# tick-mk-5_0_1.net
KiCad netlist of a schematic drawn in EAGLE
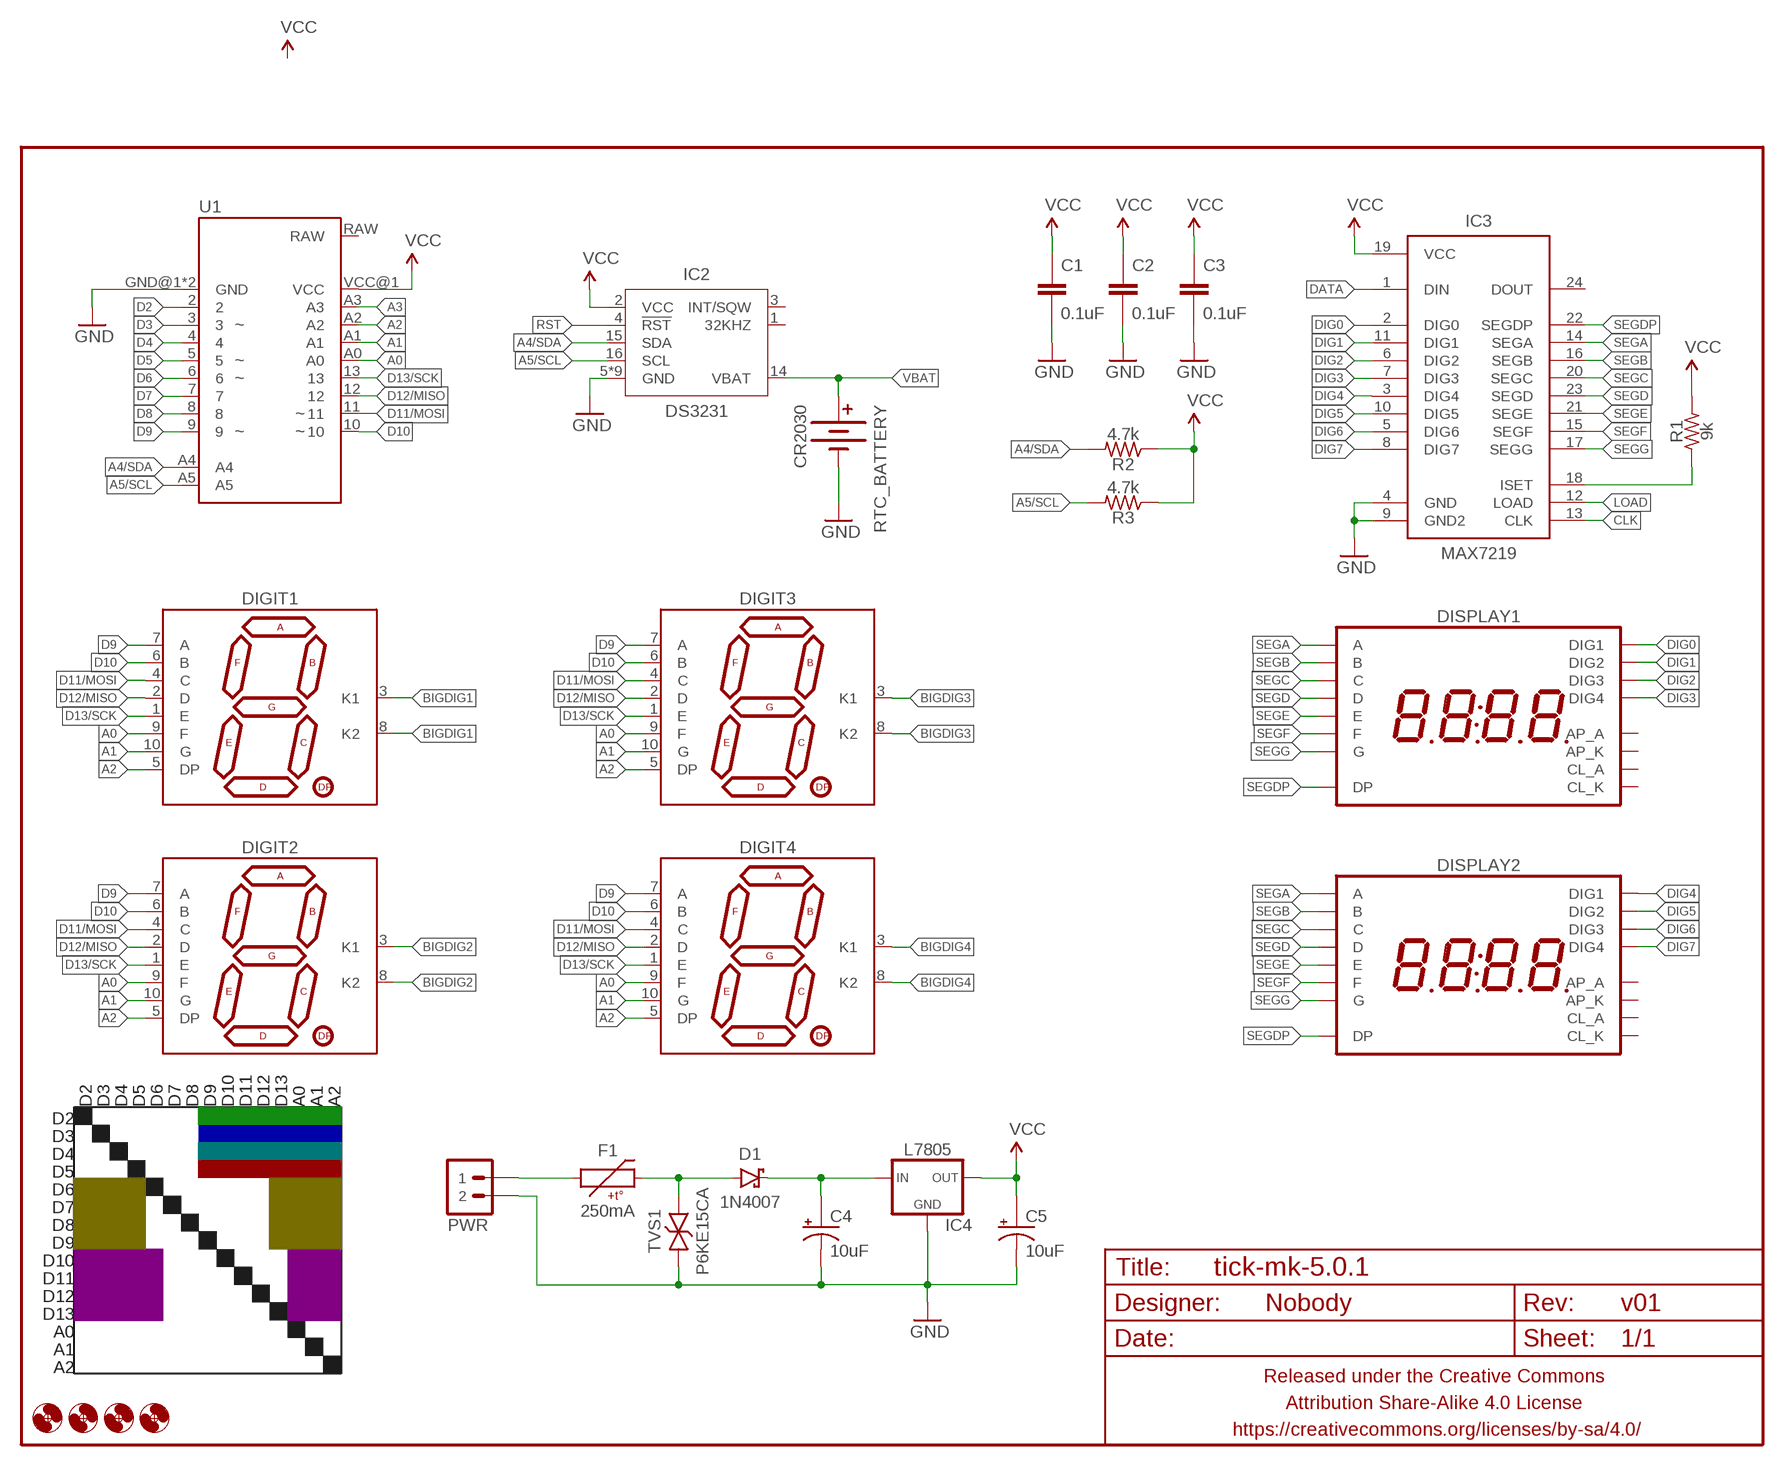
[diagram p0: schematic, sheet 1]

(export (version "E")
  (design (tool "Eeschema 10.0.6"))
  (components
    (comp (ref "C1")
      (value "0.1uF")
      (footprint "eagle-import:C025-024X044")
      (libsource (lib "eagle-import") (part "CAPACITOR-CERAMIC025-024X044"))
    )
    (comp (ref "C2")
      (value "0.1uF")
      (footprint "eagle-import:C025-024X044")
      (libsource (lib "eagle-import") (part "CAPACITOR-CERAMIC025-024X044"))
    )
    (comp (ref "C3")
      (value "0.1uF")
      (footprint "eagle-import:C0603")
      (libsource (lib "eagle-import") (part "CAPACITOR-CERAMICC0603"))
    )
    (comp (ref "C4")
      (value "10uF")
      (footprint "eagle-import:E2-5")
      (libsource (lib "eagle-import") (part "CAPACITOR-POLARIZEDE2-5"))
    )
    (comp (ref "C5")
      (value "10uF")
      (footprint "eagle-import:E2-5")
      (libsource (lib "eagle-import") (part "CAPACITOR-POLARIZEDE2-5"))
    )
    (comp (ref "D1")
      (value "1N4007")
      (footprint "eagle-import:DIODE-10.16MM")
      (libsource (lib "eagle-import") (part "DIODE-SCHOTTKYPTH-10.16MM"))
    )
    (comp (ref "DIGIT1")
      (value "7SEG_1DIGPTH-25.4MM-BARE")
      (footprint "eagle-import:7SEG_1DIG_25.4MM_NOSILK")
      (libsource (lib "eagle-import") (part "7SEG_1DIGPTH-25.4MM-BARE"))
    )
    (comp (ref "DIGIT2")
      (value "7SEG_1DIGPTH-25.4MM-BARE")
      (footprint "eagle-import:7SEG_1DIG_25.4MM_NOSILK")
      (libsource (lib "eagle-import") (part "7SEG_1DIGPTH-25.4MM-BARE"))
    )
    (comp (ref "DIGIT3")
      (value "7SEG_1DIGPTH-25.4MM-BARE")
      (footprint "eagle-import:7SEG_1DIG_25.4MM_NOSILK")
      (libsource (lib "eagle-import") (part "7SEG_1DIGPTH-25.4MM-BARE"))
    )
    (comp (ref "DIGIT4")
      (value "7SEG_1DIGPTH-25.4MM-BARE")
      (footprint "eagle-import:7SEG_1DIG_25.4MM_NOSILK")
      (libsource (lib "eagle-import") (part "7SEG_1DIGPTH-25.4MM-BARE"))
    )
    (comp (ref "DISPLAY1")
      (value "7SEG_4DIGIT_COLON_APOS")
      (footprint "eagle-import:7SEG_4DIG_10MM")
      (libsource (lib "eagle-import") (part "7SEG_4DIGIT_COLON_APOS"))
    )
    (comp (ref "DISPLAY2")
      (value "7SEG_4DIGIT_COLON_APOS")
      (footprint "eagle-import:7SEG_4DIG_10MM")
      (libsource (lib "eagle-import") (part "7SEG_4DIGIT_COLON_APOS"))
    )
    (comp (ref "F1")
      (value "250mA")
      (footprint "eagle-import:PTC-PTH-5.08MM")
      (libsource (lib "eagle-import") (part "PTCPTH-5.08MM"))
    )
    (comp (ref "FRAME1")
      (value "FRAME-LETTERNO_PACKAGE")
      (footprint "eagle-import:DUMMY")
      (fields (field (name "DESIGNER") "Nobody"))
      (libsource (lib "eagle-import") (part "FRAME-LETTERNO_PACKAGE"))
    )
    (comp (ref "H1")
      (value "HOLE2,5")
      (footprint "eagle-import:2,5")
      (libsource (lib "eagle-import") (part "HOLE2,5"))
    )
    (comp (ref "H2")
      (value "HOLE2,5")
      (footprint "eagle-import:2,5")
      (libsource (lib "eagle-import") (part "HOLE2,5"))
    )
    (comp (ref "H3")
      (value "HOLE2,5")
      (footprint "eagle-import:2,5")
      (libsource (lib "eagle-import") (part "HOLE2,5"))
    )
    (comp (ref "H4")
      (value "HOLE2,5")
      (footprint "eagle-import:2,5")
      (libsource (lib "eagle-import") (part "HOLE2,5"))
    )
    (comp (ref "IC2")
      (value "DS3231")
      (footprint "eagle-import:SO16W")
      (libsource (lib "eagle-import") (part "DS3231"))
    )
    (comp (ref "IC3")
      (value "MAX7219")
      (footprint "eagle-import:SO24W")
      (libsource (lib "eagle-import") (part "MAX7219SOIC-W"))
    )
    (comp (ref "IC4")
      (value "L7805")
      (footprint "eagle-import:TO220-IGO-THERMPAD")
      (libsource (lib "eagle-import") (part "V_REG_78XXTO-220-THERMPAD"))
    )
    (comp (ref "PWR")
      (value "M02JST-PTH-RA-L+")
      (footprint "eagle-import:JST-2-PH-RA-PTH-L+")
      (libsource (lib "eagle-import") (part "M02JST-PTH-RA-L+"))
    )
    (comp (ref "R1")
      (value "9k")
      (footprint "eagle-import:R0603")
      (libsource (lib "eagle-import") (part "RESISTORR0603"))
    )
    (comp (ref "R2")
      (value "4.7k")
      (footprint "eagle-import:RESISTOR-AXIAL-PTH-6.35MM")
      (libsource (lib "eagle-import") (part "RESISTORPTH-AXIAL-6.35MM"))
    )
    (comp (ref "R3")
      (value "4.7k")
      (footprint "eagle-import:RESISTOR-AXIAL-PTH-6.35MM")
      (libsource (lib "eagle-import") (part "RESISTORPTH-AXIAL-6.35MM"))
    )
    (comp (ref "RTC_BATTERY")
      (value "CR2030")
      (footprint "eagle-import:BATTCON_20MM_MINE_STAHPIT")
      (libsource (lib "eagle-import") (part "BATTERY20MM_SMD_TIGHT"))
    )
    (comp (ref "TVS1")
      (value "P6KE15CA")
      (footprint "eagle-import:DO-41-TVS-BI-10.16MM")
      (libsource (lib "eagle-import") (part "TVSDO-41-10.16MM"))
    )
    (comp (ref "U1")
      (value "ARDUINO_PRO_MINI_TICK2")
      (footprint "eagle-import:ARDUINO_PRO_MINI_TICK2")
      (libsource (lib "eagle-import") (part "ARDUINO_PRO_MINI_TICK2"))
    )
  )
  (nets
    (net (code "1") (name "A0") (class "Default")
      (node (ref "DIGIT1") (pin "9") (pinfunction "F_9") (pintype "bidirectional"))
      (node (ref "DIGIT2") (pin "9") (pinfunction "F_9") (pintype "bidirectional"))
      (node (ref "DIGIT3") (pin "9") (pinfunction "F_9") (pintype "bidirectional"))
      (node (ref "DIGIT4") (pin "9") (pinfunction "F_9") (pintype "bidirectional"))
      (node (ref "U1") (pin "A0") (pinfunction "A0_A0") (pintype "bidirectional"))
    )
    (net (code "2") (name "A1") (class "Default")
      (node (ref "DIGIT1") (pin "10") (pinfunction "G_10") (pintype "bidirectional"))
      (node (ref "DIGIT2") (pin "10") (pinfunction "G_10") (pintype "bidirectional"))
      (node (ref "DIGIT3") (pin "10") (pinfunction "G_10") (pintype "bidirectional"))
      (node (ref "DIGIT4") (pin "10") (pinfunction "G_10") (pintype "bidirectional"))
      (node (ref "U1") (pin "A1") (pinfunction "A1_A1") (pintype "bidirectional"))
    )
    (net (code "3") (name "A2") (class "Default")
      (node (ref "DIGIT1") (pin "5") (pinfunction "DP_5") (pintype "bidirectional"))
      (node (ref "DIGIT2") (pin "5") (pinfunction "DP_5") (pintype "bidirectional"))
      (node (ref "DIGIT3") (pin "5") (pinfunction "DP_5") (pintype "bidirectional"))
      (node (ref "DIGIT4") (pin "5") (pinfunction "DP_5") (pintype "bidirectional"))
      (node (ref "U1") (pin "A2") (pinfunction "A2_A2") (pintype "bidirectional"))
    )
    (net (code "4") (name "A3") (class "Default")
      (node (ref "U1") (pin "A3") (pinfunction "A3_A3") (pintype "bidirectional"))
    )
    (net (code "5") (name "A4{slash}SDA") (class "Default")
      (node (ref "IC2") (pin "15") (pinfunction "SDA_15") (pintype "bidirectional"))
      (node (ref "R2") (pin "P$2") (pinfunction "2_P$2") (pintype "passive"))
      (node (ref "U1") (pin "A4") (pinfunction "A4_A4") (pintype "bidirectional"))
    )
    (net (code "6") (name "A5{slash}SCL") (class "Default")
      (node (ref "IC2") (pin "16") (pinfunction "SCL_16") (pintype "bidirectional"))
      (node (ref "R3") (pin "P$2") (pinfunction "2_P$2") (pintype "passive"))
      (node (ref "U1") (pin "A5") (pinfunction "A5_A5") (pintype "bidirectional"))
    )
    (net (code "7") (name "BIGDIG1") (class "Default")
      (node (ref "DIGIT1") (pin "3") (pinfunction "K1_3") (pintype "bidirectional"))
      (node (ref "DIGIT1") (pin "8") (pinfunction "K2_8") (pintype "bidirectional"))
    )
    (net (code "8") (name "BIGDIG2") (class "Default")
      (node (ref "DIGIT2") (pin "3") (pinfunction "K1_3") (pintype "bidirectional"))
      (node (ref "DIGIT2") (pin "8") (pinfunction "K2_8") (pintype "bidirectional"))
    )
    (net (code "9") (name "BIGDIG3") (class "Default")
      (node (ref "DIGIT3") (pin "3") (pinfunction "K1_3") (pintype "bidirectional"))
      (node (ref "DIGIT3") (pin "8") (pinfunction "K2_8") (pintype "bidirectional"))
    )
    (net (code "10") (name "BIGDIG4") (class "Default")
      (node (ref "DIGIT4") (pin "3") (pinfunction "K1_3") (pintype "bidirectional"))
      (node (ref "DIGIT4") (pin "8") (pinfunction "K2_8") (pintype "bidirectional"))
    )
    (net (code "11") (name "CLK") (class "Default")
      (node (ref "IC3") (pin "13") (pinfunction "CLK_13") (pintype "bidirectional"))
    )
    (net (code "12") (name "D2") (class "Default")
      (node (ref "U1") (pin "2") (pinfunction "2_2") (pintype "bidirectional"))
    )
    (net (code "13") (name "D3") (class "Default")
      (node (ref "U1") (pin "3") (pinfunction "3_3") (pintype "bidirectional"))
    )
    (net (code "14") (name "D4") (class "Default")
      (node (ref "U1") (pin "4") (pinfunction "4_4") (pintype "bidirectional"))
    )
    (net (code "15") (name "D5") (class "Default")
      (node (ref "U1") (pin "5") (pinfunction "5_5") (pintype "bidirectional"))
    )
    (net (code "16") (name "D6") (class "Default")
      (node (ref "U1") (pin "6") (pinfunction "6_6") (pintype "bidirectional"))
    )
    (net (code "17") (name "D7") (class "Default")
      (node (ref "U1") (pin "7") (pinfunction "7_7") (pintype "bidirectional"))
    )
    (net (code "18") (name "D8") (class "Default")
      (node (ref "U1") (pin "8") (pinfunction "8_8") (pintype "bidirectional"))
    )
    (net (code "19") (name "D9") (class "Default")
      (node (ref "DIGIT1") (pin "7") (pinfunction "A_7") (pintype "bidirectional"))
      (node (ref "DIGIT2") (pin "7") (pinfunction "A_7") (pintype "bidirectional"))
      (node (ref "DIGIT3") (pin "7") (pinfunction "A_7") (pintype "bidirectional"))
      (node (ref "DIGIT4") (pin "7") (pinfunction "A_7") (pintype "bidirectional"))
      (node (ref "U1") (pin "9") (pinfunction "9_9") (pintype "bidirectional"))
    )
    (net (code "20") (name "D10") (class "Default")
      (node (ref "DIGIT1") (pin "6") (pinfunction "B_6") (pintype "bidirectional"))
      (node (ref "DIGIT2") (pin "6") (pinfunction "B_6") (pintype "bidirectional"))
      (node (ref "DIGIT3") (pin "6") (pinfunction "B_6") (pintype "bidirectional"))
      (node (ref "DIGIT4") (pin "6") (pinfunction "B_6") (pintype "bidirectional"))
      (node (ref "U1") (pin "10") (pinfunction "10_10") (pintype "bidirectional"))
    )
    (net (code "21") (name "D11{slash}MOSI") (class "Default")
      (node (ref "DIGIT1") (pin "4") (pinfunction "C_4") (pintype "bidirectional"))
      (node (ref "DIGIT2") (pin "4") (pinfunction "C_4") (pintype "bidirectional"))
      (node (ref "DIGIT3") (pin "4") (pinfunction "C_4") (pintype "bidirectional"))
      (node (ref "DIGIT4") (pin "4") (pinfunction "C_4") (pintype "bidirectional"))
      (node (ref "U1") (pin "11") (pinfunction "11_11") (pintype "bidirectional"))
    )
    (net (code "22") (name "D12{slash}MISO") (class "Default")
      (node (ref "DIGIT1") (pin "2") (pinfunction "D_2") (pintype "bidirectional"))
      (node (ref "DIGIT2") (pin "2") (pinfunction "D_2") (pintype "bidirectional"))
      (node (ref "DIGIT3") (pin "2") (pinfunction "D_2") (pintype "bidirectional"))
      (node (ref "DIGIT4") (pin "2") (pinfunction "D_2") (pintype "bidirectional"))
      (node (ref "U1") (pin "12") (pinfunction "12_12") (pintype "bidirectional"))
    )
    (net (code "23") (name "D13{slash}SCK") (class "Default")
      (node (ref "DIGIT1") (pin "1") (pinfunction "E_1") (pintype "bidirectional"))
      (node (ref "DIGIT2") (pin "1") (pinfunction "E_1") (pintype "bidirectional"))
      (node (ref "DIGIT3") (pin "1") (pinfunction "E_1") (pintype "bidirectional"))
      (node (ref "DIGIT4") (pin "1") (pinfunction "E_1") (pintype "bidirectional"))
      (node (ref "U1") (pin "13") (pinfunction "13_13") (pintype "bidirectional"))
    )
    (net (code "24") (name "DATA") (class "Default")
      (node (ref "IC3") (pin "1") (pinfunction "DIN_1") (pintype "bidirectional"))
    )
    (net (code "25") (name "DIG0") (class "Default")
      (node (ref "DISPLAY1") (pin "1") (pinfunction "DIG1_1") (pintype "passive"))
      (node (ref "IC3") (pin "2") (pinfunction "DIG0_2") (pintype "bidirectional"))
    )
    (net (code "26") (name "DIG1") (class "Default")
      (node (ref "DISPLAY1") (pin "2") (pinfunction "DIG2_2") (pintype "passive"))
      (node (ref "IC3") (pin "11") (pinfunction "DIG1_11") (pintype "bidirectional"))
    )
    (net (code "27") (name "DIG2") (class "Default")
      (node (ref "DISPLAY1") (pin "6") (pinfunction "DIG3_6") (pintype "passive"))
      (node (ref "IC3") (pin "6") (pinfunction "DIG2_6") (pintype "bidirectional"))
    )
    (net (code "28") (name "DIG3") (class "Default")
      (node (ref "DISPLAY1") (pin "8") (pinfunction "DIG4_8") (pintype "passive"))
      (node (ref "IC3") (pin "7") (pinfunction "DIG3_7") (pintype "bidirectional"))
    )
    (net (code "29") (name "DIG4") (class "Default")
      (node (ref "DISPLAY2") (pin "1") (pinfunction "DIG1_1") (pintype "passive"))
      (node (ref "IC3") (pin "3") (pinfunction "DIG4_3") (pintype "bidirectional"))
    )
    (net (code "30") (name "DIG5") (class "Default")
      (node (ref "DISPLAY2") (pin "2") (pinfunction "DIG2_2") (pintype "passive"))
      (node (ref "IC3") (pin "10") (pinfunction "DIG5_10") (pintype "bidirectional"))
    )
    (net (code "31") (name "DIG6") (class "Default")
      (node (ref "DISPLAY2") (pin "6") (pinfunction "DIG3_6") (pintype "passive"))
      (node (ref "IC3") (pin "5") (pinfunction "DIG6_5") (pintype "bidirectional"))
    )
    (net (code "32") (name "DIG7") (class "Default")
      (node (ref "DISPLAY2") (pin "8") (pinfunction "DIG4_8") (pintype "passive"))
      (node (ref "IC3") (pin "8") (pinfunction "DIG7_8") (pintype "bidirectional"))
    )
    (net (code "33") (name "GND") (class "Default")
      (node (ref "C1") (pin "2") (pinfunction "2_2") (pintype "passive"))
      (node (ref "C2") (pin "2") (pinfunction "2_2") (pintype "passive"))
      (node (ref "C3") (pin "2") (pinfunction "2_2") (pintype "passive"))
      (node (ref "C4") (pin "-") (pinfunction "-_-") (pintype "passive"))
      (node (ref "C5") (pin "-") (pinfunction "-_-") (pintype "passive"))
      (node (ref "IC2") (pin "10") (pinfunction "GND_10") (pintype "bidirectional"))
      (node (ref "IC2") (pin "11") (pinfunction "GND_11") (pintype "bidirectional"))
      (node (ref "IC2") (pin "12") (pinfunction "GND_12") (pintype "bidirectional"))
      (node (ref "IC2") (pin "13") (pinfunction "GND_13") (pintype "bidirectional"))
      (node (ref "IC2") (pin "5") (pinfunction "GND_5") (pintype "bidirectional"))
      (node (ref "IC2") (pin "6") (pinfunction "GND_6") (pintype "bidirectional"))
      (node (ref "IC2") (pin "7") (pinfunction "GND_7") (pintype "bidirectional"))
      (node (ref "IC2") (pin "8") (pinfunction "GND_8") (pintype "bidirectional"))
      (node (ref "IC2") (pin "9") (pinfunction "GND_9") (pintype "bidirectional"))
      (node (ref "IC3") (pin "4") (pinfunction "GND_4") (pintype "bidirectional"))
      (node (ref "IC3") (pin "9") (pinfunction "GND2_9") (pintype "bidirectional"))
      (node (ref "IC4") (pin "4") (pinfunction "GND_4") (pintype "bidirectional"))
      (node (ref "IC4") (pin "GND") (pinfunction "GND_GND") (pintype "bidirectional"))
      (node (ref "PWR") (pin "2") (pinfunction "2_2") (pintype "passive"))
      (node (ref "RTC_BATTERY") (pin "BOTTOM") (pinfunction "-_BOTTOM") (pintype "power_in"))
      (node (ref "TVS1") (pin "P$1") (pinfunction "1_P$1") (pintype "passive"))
      (node (ref "U1") (pin "GND@1") (pinfunction "GND_GND@1") (pintype "bidirectional"))
      (node (ref "U1") (pin "GND@2") (pinfunction "GND_GND@2") (pintype "bidirectional"))
    )
    (net (code "34") (name "LOAD") (class "Default")
      (node (ref "IC3") (pin "12") (pinfunction "LOAD_12") (pintype "bidirectional"))
    )
    (net (code "35") (name "Net-(C4-Pad+)") (class "Default")
      (node (ref "C4") (pin "+") (pinfunction "+_+") (pintype "passive"))
      (node (ref "D1") (pin "C") (pinfunction "C_C") (pintype "passive"))
      (node (ref "IC4") (pin "IN") (pinfunction "IN_IN") (pintype "bidirectional"))
    )
    (net (code "36") (name "Net-(F1-1)") (class "Default")
      (node (ref "F1") (pin "P$1") (pinfunction "1_P$1") (pintype "passive"))
      (node (ref "PWR") (pin "1") (pinfunction "1_1") (pintype "passive"))
    )
    (net (code "37") (name "Net-(F1-2)") (class "Default")
      (node (ref "D1") (pin "A") (pinfunction "A_A") (pintype "passive"))
      (node (ref "F1") (pin "P$2") (pinfunction "2_P$2") (pintype "passive"))
      (node (ref "TVS1") (pin "P$2") (pinfunction "2_P$2") (pintype "passive"))
    )
    (net (code "38") (name "Net-(IC3-ISET)") (class "Default")
      (node (ref "IC3") (pin "18") (pinfunction "ISET_18") (pintype "bidirectional"))
      (node (ref "R1") (pin "1") (pinfunction "1_1") (pintype "passive"))
    )
    (net (code "39") (name "RST") (class "Default")
      (node (ref "IC2") (pin "4") (pinfunction "~{RST}_4") (pintype "bidirectional"))
    )
    (net (code "40") (name "SEGA") (class "Default")
      (node (ref "DISPLAY1") (pin "14") (pinfunction "A_14") (pintype "passive"))
      (node (ref "DISPLAY2") (pin "14") (pinfunction "A_14") (pintype "passive"))
      (node (ref "IC3") (pin "14") (pinfunction "SEGA_14") (pintype "bidirectional"))
    )
    (net (code "41") (name "SEGB") (class "Default")
      (node (ref "DISPLAY1") (pin "16") (pinfunction "B_16") (pintype "passive"))
      (node (ref "DISPLAY2") (pin "16") (pinfunction "B_16") (pintype "passive"))
      (node (ref "IC3") (pin "16") (pinfunction "SEGB_16") (pintype "bidirectional"))
    )
    (net (code "42") (name "SEGC") (class "Default")
      (node (ref "DISPLAY1") (pin "13") (pinfunction "C_13") (pintype "passive"))
      (node (ref "DISPLAY2") (pin "13") (pinfunction "C_13") (pintype "passive"))
      (node (ref "IC3") (pin "20") (pinfunction "SEGC_20") (pintype "bidirectional"))
    )
    (net (code "43") (name "SEGD") (class "Default")
      (node (ref "DISPLAY1") (pin "3") (pinfunction "D_3") (pintype "passive"))
      (node (ref "DISPLAY2") (pin "3") (pinfunction "D_3") (pintype "passive"))
      (node (ref "IC3") (pin "23") (pinfunction "SEGD_23") (pintype "bidirectional"))
    )
    (net (code "44") (name "SEGDP") (class "Default")
      (node (ref "DISPLAY1") (pin "7") (pinfunction "DP_7") (pintype "passive"))
      (node (ref "DISPLAY2") (pin "7") (pinfunction "DP_7") (pintype "passive"))
      (node (ref "IC3") (pin "22") (pinfunction "SEGDP_22") (pintype "bidirectional"))
    )
    (net (code "45") (name "SEGE") (class "Default")
      (node (ref "DISPLAY1") (pin "5") (pinfunction "E_5") (pintype "passive"))
      (node (ref "DISPLAY2") (pin "5") (pinfunction "E_5") (pintype "passive"))
      (node (ref "IC3") (pin "21") (pinfunction "SEGE_21") (pintype "bidirectional"))
    )
    (net (code "46") (name "SEGF") (class "Default")
      (node (ref "DISPLAY1") (pin "11") (pinfunction "F_11") (pintype "passive"))
      (node (ref "DISPLAY2") (pin "11") (pinfunction "F_11") (pintype "passive"))
      (node (ref "IC3") (pin "15") (pinfunction "SEGF_15") (pintype "bidirectional"))
    )
    (net (code "47") (name "SEGG") (class "Default")
      (node (ref "DISPLAY1") (pin "15") (pinfunction "G_15") (pintype "passive"))
      (node (ref "DISPLAY2") (pin "15") (pinfunction "G_15") (pintype "passive"))
      (node (ref "IC3") (pin "17") (pinfunction "SEGG_17") (pintype "bidirectional"))
    )
    (net (code "48") (name "VBAT") (class "Default")
      (node (ref "IC2") (pin "14") (pinfunction "VBAT_14") (pintype "bidirectional"))
      (node (ref "RTC_BATTERY") (pin "TOP@1") (pinfunction "+_TOP@1") (pintype "power_in"))
      (node (ref "RTC_BATTERY") (pin "TOP@2") (pinfunction "+_TOP@2") (pintype "power_in"))
    )
    (net (code "49") (name "VCC") (class "Default")
      (node (ref "C1") (pin "1") (pinfunction "1_1") (pintype "passive"))
      (node (ref "C2") (pin "1") (pinfunction "1_1") (pintype "passive"))
      (node (ref "C3") (pin "1") (pinfunction "1_1") (pintype "passive"))
      (node (ref "C5") (pin "+") (pinfunction "+_+") (pintype "passive"))
      (node (ref "IC2") (pin "2") (pinfunction "VCC_2") (pintype "bidirectional"))
      (node (ref "IC3") (pin "19") (pinfunction "VCC_19") (pintype "bidirectional"))
      (node (ref "IC4") (pin "OUT") (pinfunction "OUT_OUT") (pintype "bidirectional"))
      (node (ref "R1") (pin "2") (pinfunction "2_2") (pintype "passive"))
      (node (ref "R2") (pin "P$1") (pinfunction "1_P$1") (pintype "passive"))
      (node (ref "R3") (pin "P$1") (pinfunction "1_P$1") (pintype "passive"))
      (node (ref "U1") (pin "VCC@1") (pinfunction "VCC_VCC@1") (pintype "bidirectional"))
    )
    (net (code "50") (name "unconnected-(DISPLAY1-AP_A-Pad10)") (class "Default")
      (node (ref "DISPLAY1") (pin "10") (pinfunction "AP_A_10") (pintype "bidirectional"))
    )
    (net (code "51") (name "unconnected-(DISPLAY1-AP_K-Pad9)") (class "Default")
      (node (ref "DISPLAY1") (pin "9") (pinfunction "AP_K_9") (pintype "bidirectional"))
    )
    (net (code "52") (name "unconnected-(DISPLAY1-CL_A-Pad4)") (class "Default")
      (node (ref "DISPLAY1") (pin "4") (pinfunction "CL_A_4") (pintype "passive"))
    )
    (net (code "53") (name "unconnected-(DISPLAY1-CL_K-Pad12)") (class "Default")
      (node (ref "DISPLAY1") (pin "12") (pinfunction "CL_K_12") (pintype "passive"))
    )
    (net (code "54") (name "unconnected-(DISPLAY2-AP_A-Pad10)") (class "Default")
      (node (ref "DISPLAY2") (pin "10") (pinfunction "AP_A_10") (pintype "bidirectional"))
    )
    (net (code "55") (name "unconnected-(DISPLAY2-AP_K-Pad9)") (class "Default")
      (node (ref "DISPLAY2") (pin "9") (pinfunction "AP_K_9") (pintype "bidirectional"))
    )
    (net (code "56") (name "unconnected-(DISPLAY2-CL_A-Pad4)") (class "Default")
      (node (ref "DISPLAY2") (pin "4") (pinfunction "CL_A_4") (pintype "passive"))
    )
    (net (code "57") (name "unconnected-(DISPLAY2-CL_K-Pad12)") (class "Default")
      (node (ref "DISPLAY2") (pin "12") (pinfunction "CL_K_12") (pintype "passive"))
    )
    (net (code "58") (name "unconnected-(IC2-32KHZ-Pad1)") (class "Default")
      (node (ref "IC2") (pin "1") (pinfunction "32KHZ_1") (pintype "bidirectional"))
    )
    (net (code "59") (name "unconnected-(IC2-INT{slash}SQW-Pad3)") (class "Default")
      (node (ref "IC2") (pin "3") (pinfunction "INT/SQW_3") (pintype "bidirectional"))
    )
    (net (code "60") (name "unconnected-(IC3-DOUT-Pad24)") (class "Default")
      (node (ref "IC3") (pin "24") (pinfunction "DOUT_24") (pintype "bidirectional"))
    )
    (net (code "61") (name "unconnected-(U1-PadRAW)") (class "Default")
      (node (ref "U1") (pin "RAW") (pinfunction "RAW_RAW") (pintype "bidirectional"))
    )
  )
)
